# pcb-project.net
KiCad netlist of a schematic drawn in EasyEDA Pro
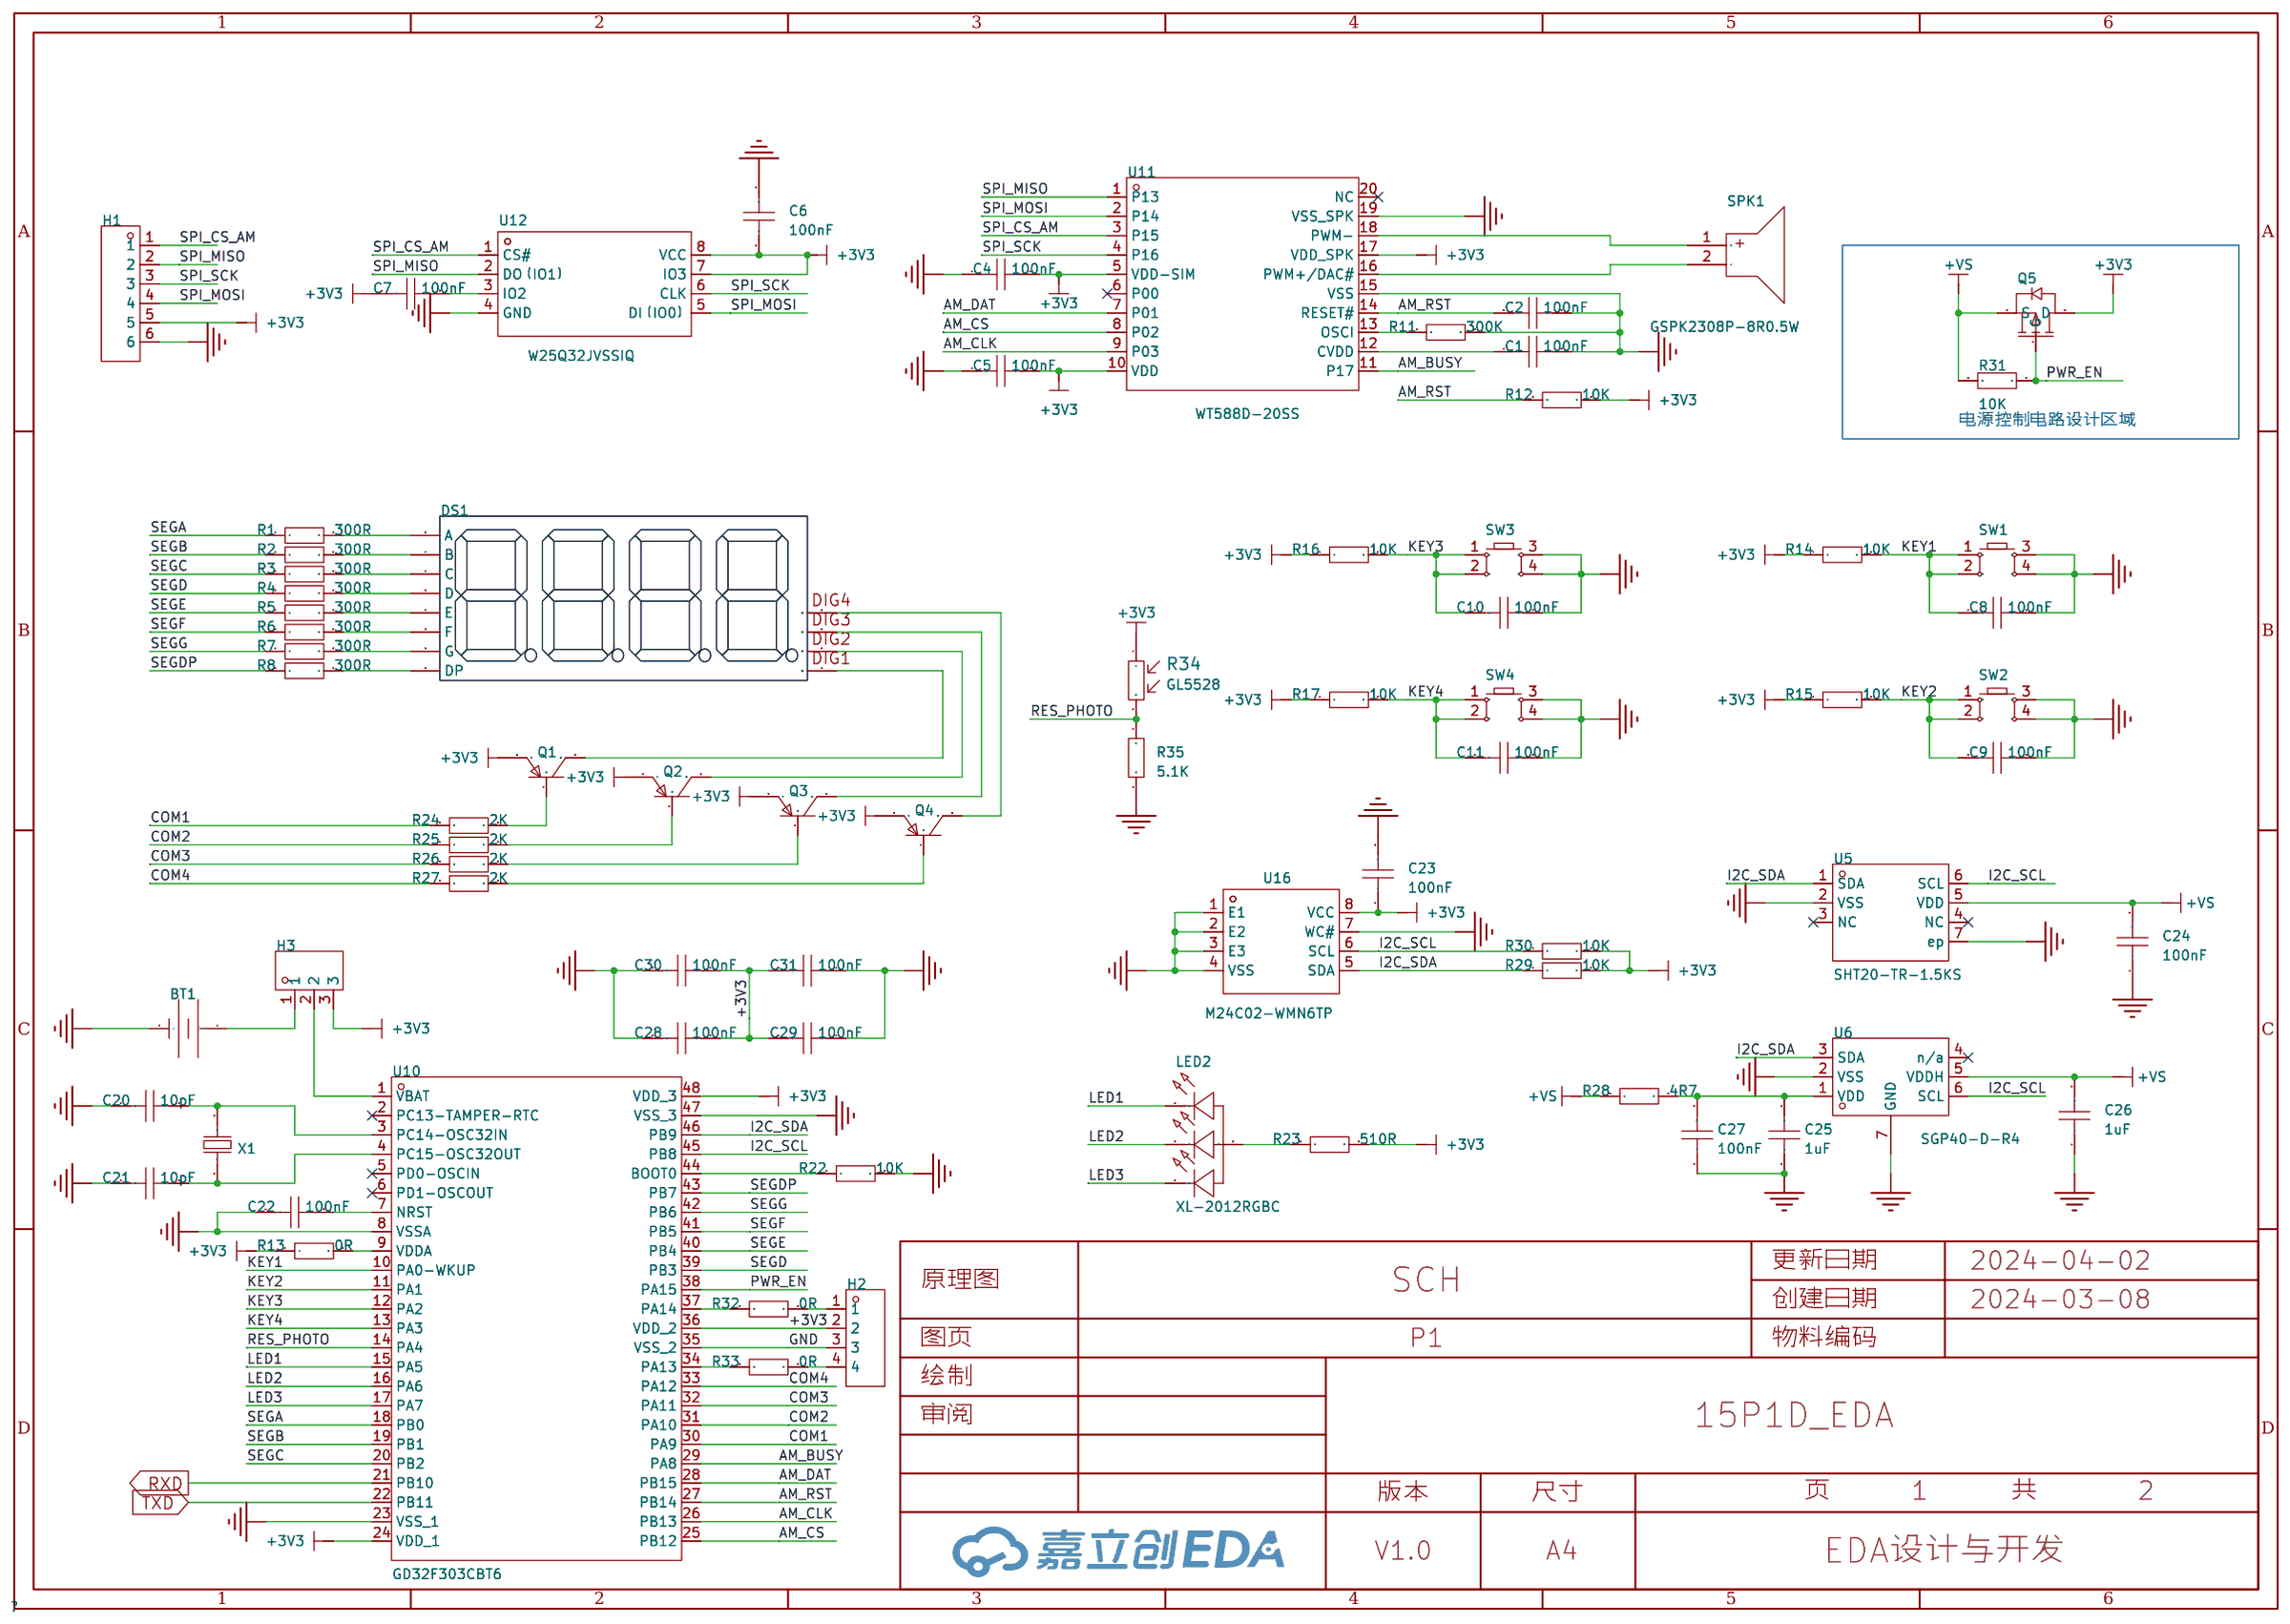
[diagram p0: P1]
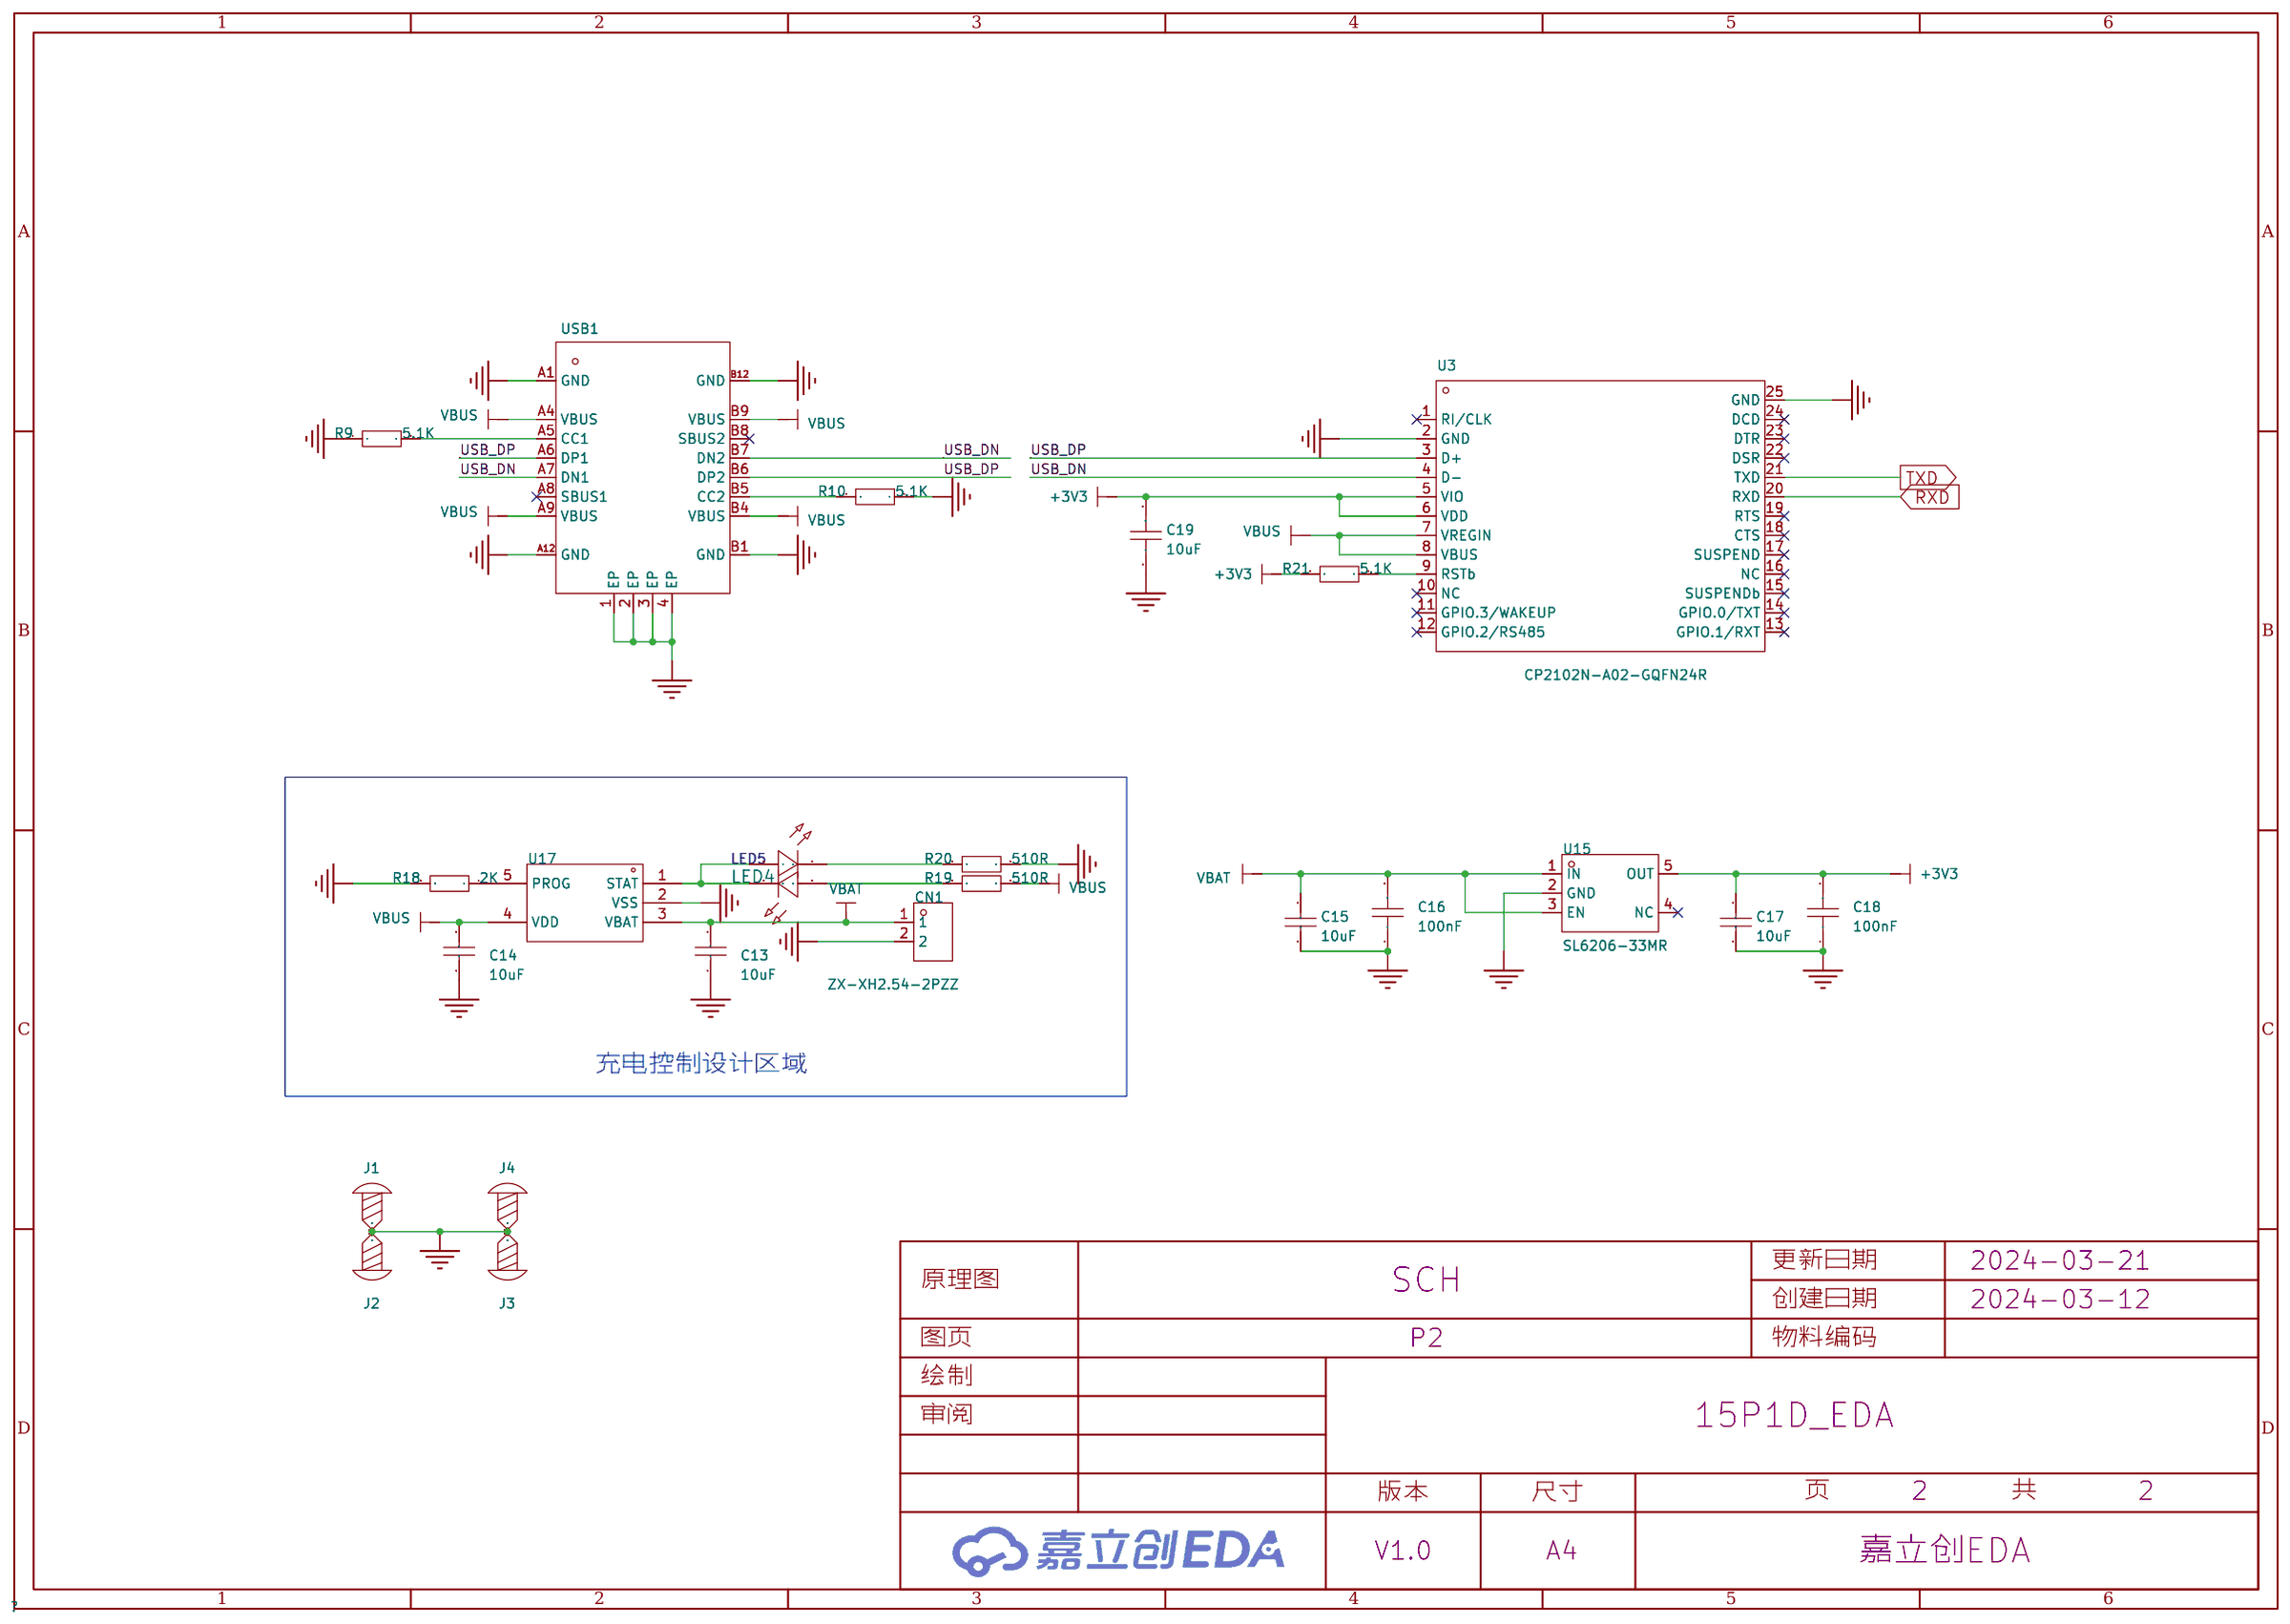
[diagram p1: P2]

(export (version "E")
  (design (tool "Eeschema 10.0.6"))
  (components
    (comp (ref "BT1")
      (value "BS-12-B3AA003")
      (footprint "easyedapro:BAT-SMD_BS-12-B3AA011")
      (description "连接器类型:电池底座;适用电池规格:CR1220;工作温度范围:-25°C~+85°C;")
      (fields (field (name "Manufacturer") "MYOUNG(美阳)"))
      (libsource (lib "easyedapro") (part "BS-12-B3AA003"))
    )
    (comp (ref "C1")
      (value "100nF")
      (footprint "easyedapro:C0805")
      (libsource (lib "easyedapro") (part "CapAcitance"))
    )
    (comp (ref "C2")
      (value "100nF")
      (footprint "easyedapro:C0805")
      (libsource (lib "easyedapro") (part "CapAcitance"))
    )
    (comp (ref "C4")
      (value "100nF")
      (footprint "easyedapro:C0805")
      (libsource (lib "easyedapro") (part "CapAcitance"))
    )
    (comp (ref "C5")
      (value "100nF")
      (footprint "easyedapro:C0805")
      (libsource (lib "easyedapro") (part "CapAcitance"))
    )
    (comp (ref "C6")
      (value "100nF")
      (footprint "easyedapro:C0805")
      (libsource (lib "easyedapro") (part "CapAcitance"))
    )
    (comp (ref "C7")
      (value "100nF")
      (footprint "easyedapro:C0805")
      (libsource (lib "easyedapro") (part "CapAcitance"))
    )
    (comp (ref "C8")
      (value "100nF")
      (footprint "easyedapro:C0805")
      (libsource (lib "easyedapro") (part "CapAcitance"))
    )
    (comp (ref "C9")
      (value "100nF")
      (footprint "easyedapro:C0805")
      (libsource (lib "easyedapro") (part "CapAcitance"))
    )
    (comp (ref "C10")
      (value "100nF")
      (footprint "easyedapro:C0805")
      (libsource (lib "easyedapro") (part "CapAcitance"))
    )
    (comp (ref "C11")
      (value "100nF")
      (footprint "easyedapro:C0805")
      (libsource (lib "easyedapro") (part "CapAcitance"))
    )
    (comp (ref "C20")
      (value "10pF")
      (footprint "easyedapro:C0805")
      (libsource (lib "easyedapro") (part "CapAcitance"))
    )
    (comp (ref "C21")
      (value "10pF")
      (footprint "easyedapro:C0805")
      (libsource (lib "easyedapro") (part "CapAcitance"))
    )
    (comp (ref "C22")
      (value "100nF")
      (footprint "easyedapro:C0805")
      (libsource (lib "easyedapro") (part "CapAcitance"))
    )
    (comp (ref "C23")
      (value "100nF")
      (footprint "easyedapro:C0805")
      (libsource (lib "easyedapro") (part "CapAcitance"))
    )
    (comp (ref "C24")
      (value "100nF")
      (footprint "easyedapro:C0805")
      (libsource (lib "easyedapro") (part "CapAcitance"))
    )
    (comp (ref "C25")
      (value "1uF")
      (footprint "easyedapro:C0805")
      (libsource (lib "easyedapro") (part "CapAcitance"))
    )
    (comp (ref "C26")
      (value "1uF")
      (footprint "easyedapro:C0805")
      (libsource (lib "easyedapro") (part "CapAcitance"))
    )
    (comp (ref "C27")
      (value "100nF")
      (footprint "easyedapro:C0805")
      (libsource (lib "easyedapro") (part "CapAcitance"))
    )
    (comp (ref "C28")
      (value "100nF")
      (footprint "easyedapro:C0805")
      (libsource (lib "easyedapro") (part "CapAcitance"))
    )
    (comp (ref "C29")
      (value "100nF")
      (footprint "easyedapro:C0805")
      (libsource (lib "easyedapro") (part "CapAcitance"))
    )
    (comp (ref "C30")
      (value "100nF")
      (footprint "easyedapro:C0805")
      (libsource (lib "easyedapro") (part "CapAcitance"))
    )
    (comp (ref "C31")
      (value "100nF")
      (footprint "easyedapro:C0805")
      (libsource (lib "easyedapro") (part "CapAcitance"))
    )
    (comp (ref "DS1")
      (value "~")
      (footprint "easyedapro:LED-SEG-TH_FJ5461AH")
      (libsource (lib "easyedapro") (part "LED_SEG_TH_0.56x4"))
    )
    (comp (ref "H1")
      (value "~")
      (footprint "easyedapro:HDR-TH_6P-P2.54-V-F")
      (libsource (lib "easyedapro") (part "Header-Female-2.54_1x6"))
    )
    (comp (ref "H2")
      (value "~")
      (footprint "easyedapro:HDR-TH_4P-P2.54-V-F")
      (libsource (lib "easyedapro") (part "2.54-1*4P母"))
    )
    (comp (ref "H3")
      (value "Jumper3")
      (footprint "easyedapro:HDR-TH_3P-P2.54-V-M-A")
      (libsource (lib "easyedapro") (part "JUMPER3"))
    )
    (comp (ref "LED2")
      (value "XL-2012RGBC")
      (footprint "easyedapro:LED-SMD_4P-L2.0-W1.3-BR")
      (fields (field (name "Manufacturer") "XINGLIGHT(成兴光)"))
      (libsource (lib "easyedapro") (part "XL-2012RGBC"))
    )
    (comp (ref "Q1")
      (value "~")
      (footprint "easyedapro:S8550P_SOT")
      (libsource (lib "easyedapro") (part "PNP"))
    )
    (comp (ref "Q2")
      (value "~")
      (footprint "easyedapro:S8550P_SOT")
      (libsource (lib "easyedapro") (part "PNP"))
    )
    (comp (ref "Q3")
      (value "~")
      (footprint "easyedapro:S8550P_SOT")
      (libsource (lib "easyedapro") (part "PNP"))
    )
    (comp (ref "Q4")
      (value "~")
      (footprint "easyedapro:S8550P_SOT")
      (libsource (lib "easyedapro") (part "PNP"))
    )
    (comp (ref "Q5")
      (value "~")
      (footprint "easyedapro:AO3401A_SOT-23-3")
      (libsource (lib "easyedapro") (part "P_MOS"))
    )
    (comp (ref "R1") (value "300R") (footprint "easyedapro:R0805") (libsource (lib "easyedapro") (part "电阻")))
    (comp (ref "R2") (value "300R") (footprint "easyedapro:R0805") (libsource (lib "easyedapro") (part "电阻")))
    (comp (ref "R3") (value "300R") (footprint "easyedapro:R0805") (libsource (lib "easyedapro") (part "电阻")))
    (comp (ref "R4") (value "300R") (footprint "easyedapro:R0805") (libsource (lib "easyedapro") (part "电阻")))
    (comp (ref "R5") (value "300R") (footprint "easyedapro:R0805") (libsource (lib "easyedapro") (part "电阻")))
    (comp (ref "R6") (value "300R") (footprint "easyedapro:R0805") (libsource (lib "easyedapro") (part "电阻")))
    (comp (ref "R7") (value "300R") (footprint "easyedapro:R0805") (libsource (lib "easyedapro") (part "电阻")))
    (comp (ref "R8") (value "300R") (footprint "easyedapro:R0805") (libsource (lib "easyedapro") (part "电阻")))
    (comp (ref "R11")
      (value "300K")
      (footprint "easyedapro:R0805")
      (libsource (lib "easyedapro") (part "电阻"))
    )
    (comp (ref "R12") (value "10K") (footprint "easyedapro:R0805") (libsource (lib "easyedapro") (part "电阻")))
    (comp (ref "R13") (value "0R") (footprint "easyedapro:R0805") (libsource (lib "easyedapro") (part "电阻")))
    (comp (ref "R14") (value "10K") (footprint "easyedapro:R0805") (libsource (lib "easyedapro") (part "电阻")))
    (comp (ref "R15") (value "10K") (footprint "easyedapro:R0805") (libsource (lib "easyedapro") (part "电阻")))
    (comp (ref "R16") (value "10K") (footprint "easyedapro:R0805") (libsource (lib "easyedapro") (part "电阻")))
    (comp (ref "R17") (value "10K") (footprint "easyedapro:R0805") (libsource (lib "easyedapro") (part "电阻")))
    (comp (ref "R22") (value "10K") (footprint "easyedapro:R0805") (libsource (lib "easyedapro") (part "电阻")))
    (comp (ref "R23")
      (value "510R")
      (footprint "easyedapro:R0805")
      (libsource (lib "easyedapro") (part "电阻"))
    )
    (comp (ref "R24") (value "2K") (footprint "easyedapro:R0805") (libsource (lib "easyedapro") (part "电阻")))
    (comp (ref "R25") (value "2K") (footprint "easyedapro:R0805") (libsource (lib "easyedapro") (part "电阻")))
    (comp (ref "R26") (value "2K") (footprint "easyedapro:R0805") (libsource (lib "easyedapro") (part "电阻")))
    (comp (ref "R27") (value "2K") (footprint "easyedapro:R0805") (libsource (lib "easyedapro") (part "电阻")))
    (comp (ref "R28") (value "4R7") (footprint "easyedapro:R0805") (libsource (lib "easyedapro") (part "电阻")))
    (comp (ref "R29") (value "10K") (footprint "easyedapro:R0805") (libsource (lib "easyedapro") (part "电阻")))
    (comp (ref "R30") (value "10K") (footprint "easyedapro:R0805") (libsource (lib "easyedapro") (part "电阻")))
    (comp (ref "R31") (value "10K") (footprint "easyedapro:R0805") (libsource (lib "easyedapro") (part "电阻")))
    (comp (ref "R32") (value "0R") (footprint "easyedapro:R0805") (libsource (lib "easyedapro") (part "电阻")))
    (comp (ref "R33") (value "0R") (footprint "easyedapro:R0805") (libsource (lib "easyedapro") (part "电阻")))
    (comp (ref "R34")
      (value "GL5528")
      (footprint "easyedapro:RES-TH_L5.1-W4.3-P3.40-D0.5")
      (description "暗电阻:1MΩ;亮电阻 @ 10Lux:8kΩ~20kΩ;光谱峰值(波长):540nm;")
      (fields (field (name "Manufacturer") "森霸"))
      (libsource (lib "easyedapro") (part "GL5528"))
    )
    (comp (ref "R35")
      (value "5.1K")
      (footprint "easyedapro:R0805")
      (libsource (lib "easyedapro") (part "电阻"))
    )
    (comp (ref "SPK1")
      (value "GSPK2308P-8R0.5W")
      (footprint "easyedapro:SPK-TH_BD23.0-P10.00-D0.8-L-RD")
      (fields (field (name "Manufacturer") "INGHAi(赢海)"))
      (libsource (lib "easyedapro") (part "GSPK2308P-8R0.5W"))
    )
    (comp (ref "SW1")
      (value "~")
      (footprint "easyedapro:Key_SMD_12x12x7.3")
      (libsource (lib "easyedapro") (part "轻触按键"))
    )
    (comp (ref "SW2")
      (value "~")
      (footprint "easyedapro:Key_SMD_12x12x7.3")
      (libsource (lib "easyedapro") (part "轻触按键"))
    )
    (comp (ref "SW3")
      (value "~")
      (footprint "easyedapro:Key_SMD_12x12x7.3")
      (libsource (lib "easyedapro") (part "轻触按键"))
    )
    (comp (ref "SW4")
      (value "~")
      (footprint "easyedapro:Key_SMD_12x12x7.3")
      (libsource (lib "easyedapro") (part "轻触按键"))
    )
    (comp (ref "U5")
      (value "SHT20-TR-1.5KS")
      (footprint "easyedapro:DFN-6_L3.0-W3.0-P0.95-TR-EP")
      (description "接口类型:I2C;")
      (fields (field (name "Manufacturer") "Sensirion(瑞士盛思锐)"))
      (libsource (lib "easyedapro") (part "SHT20"))
    )
    (comp (ref "U6")
      (value "SGP40-D-R4")
      (footprint "easyedapro:DFN-6_L2.4-W2.4-P0.80-TL-EP")
      (description "气体类型:空气质量;精度:-;")
      (fields (field (name "Manufacturer") "Sensirion(瑞士盛思锐)"))
      (libsource (lib "easyedapro") (part "SGP40-D-R4"))
    )
    (comp (ref "U10")
      (value "GD32F303CBT6")
      (footprint "easyedapro:LQFP-48_L7.0-W7.0-P0.50-LS9.0-BL")
      (description "CPU内核:CM4;程序存储容量:128KB;RAM总容量:32KB;GPIO端口数量:37;工作电压范围:-;CPU最大主频:120MHz;程序存储器类型:FLASH;")
      (fields (field (name "Manufacturer") "GigaDevice(兆易创新)"))
      (libsource (lib "easyedapro") (part "GD32F303CBT6"))
    )
    (comp (ref "U11")
      (value "WT588D-20SS")
      (footprint "easyedapro:SSOP-20_L7.2-W5.3-P0.65-LS7.8-BL")
      (description "高品质语音芯片")
      (fields (field (name "Manufacturer") "WT(唯创知音)"))
      (libsource (lib "easyedapro") (part "WT588D"))
    )
    (comp (ref "U12")
      (value "W25Q32JVSSIQ")
      (footprint "easyedapro:SOIC-8_L5.3-W5.3-P1.27-LS8.0-BL")
      (description "接口类型:SPI;存储容量:32Mbit;")
      (fields (field (name "Manufacturer") "WINBOND(华邦)"))
      (libsource (lib "easyedapro") (part "W25Q32JVSSIQ"))
    )
    (comp (ref "U16")
      (value "M24C02-WMN6TP")
      (footprint "easyedapro:SOIC-8_L4.9-W3.9-P1.27-LS6.0-BL")
      (description "接口类型:I2C;存储容量:2Kbit;")
      (fields (field (name "Manufacturer") "ST(意法半导体)"))
      (libsource (lib "easyedapro") (part "M24C02-WMN6TP"))
    )
    (comp (ref "X1")
      (value "32.768kHz")
      (footprint "easyedapro:FC-135R_L3.2-W1.5")
      (description "晶振类型:贴片晶振;频率:32.768kHz;常温频差:±20ppm;外接负载电容:12.5pF;")
      (fields (field (name "Manufacturer Part") "Q13FC13500004") (field (name "Manufacturer") "EPSON(爱普生)"))
      (libsource (lib "easyedapro") (part "Q13FC1350000400"))
    )
    (comp (ref "C13")
      (value "10uF")
      (footprint "easyedapro:C1206")
      (description "容值:10uF;精度:±10%;额定电压:50V;材质(温度系数):X5R;")
      (fields
        (field (name "Manufacturer Part") "CL31A106KBHNNNE")
        (field (name "Manufacturer") "SAMSUNG(三星)")
      )
      (libsource (lib "easyedapro") (part "CL31A106KBHNNNE"))
    )
    (comp (ref "C14")
      (value "10uF")
      (footprint "easyedapro:C1206")
      (description "容值:10uF;精度:±10%;额定电压:50V;材质(温度系数):X5R;")
      (fields
        (field (name "Manufacturer Part") "CL31A106KBHNNNE")
        (field (name "Manufacturer") "SAMSUNG(三星)")
      )
      (libsource (lib "easyedapro") (part "CL31A106KBHNNNE"))
    )
    (comp (ref "C15")
      (value "10uF")
      (footprint "easyedapro:C1206")
      (description "容值:10uF;精度:±10%;额定电压:50V;材质(温度系数):X5R;")
      (fields
        (field (name "Manufacturer Part") "CL31A106KBHNNNE")
        (field (name "Manufacturer") "SAMSUNG(三星)")
      )
      (libsource (lib "easyedapro") (part "CL31A106KBHNNNE"))
    )
    (comp (ref "C16")
      (value "100nF")
      (footprint "easyedapro:C0805")
      (libsource (lib "easyedapro") (part "CapAcitance"))
    )
    (comp (ref "C17")
      (value "10uF")
      (footprint "easyedapro:C1206")
      (description "容值:10uF;精度:±10%;额定电压:50V;材质(温度系数):X5R;")
      (fields
        (field (name "Manufacturer Part") "CL31A106KBHNNNE")
        (field (name "Manufacturer") "SAMSUNG(三星)")
      )
      (libsource (lib "easyedapro") (part "CL31A106KBHNNNE"))
    )
    (comp (ref "C18")
      (value "100nF")
      (footprint "easyedapro:C0805")
      (libsource (lib "easyedapro") (part "CapAcitance"))
    )
    (comp (ref "C19")
      (value "10uF")
      (footprint "easyedapro:C0805")
      (libsource (lib "easyedapro") (part "CapAcitance"))
    )
    (comp (ref "CN1")
      (value "ZX-XH2.54-2PZZ")
      (footprint "easyedapro:CONN-TH_2P-P2.50_HX25003-2A")
      (fields (field (name "Manufacturer") "Megastar(兆星)"))
      (libsource (lib "easyedapro") (part "ZX-XH2.54-2PZZ"))
    )
    (comp (ref "J1") (value "~") (footprint "easyedapro:M2螺丝") (libsource (lib "easyedapro") (part "螺丝孔")))
    (comp (ref "J2") (value "~") (footprint "easyedapro:M2螺丝") (libsource (lib "easyedapro") (part "螺丝孔")))
    (comp (ref "J3") (value "~") (footprint "easyedapro:M2螺丝") (libsource (lib "easyedapro") (part "螺丝孔")))
    (comp (ref "J4") (value "~") (footprint "easyedapro:M2螺丝") (libsource (lib "easyedapro") (part "螺丝孔")))
    (comp (ref "LED4")
      (value "~")
      (footprint "easyedapro:LED_0805")
      (libsource (lib "easyedapro") (part "LED_R"))
    )
    (comp (ref "LED5")
      (value "~")
      (footprint "easyedapro:LED_0805")
      (libsource (lib "easyedapro") (part "LED_G"))
    )
    (comp (ref "R9") (value "5.1K") (footprint "easyedapro:R0805") (libsource (lib "easyedapro") (part "电阻")))
    (comp (ref "R10")
      (value "5.1K")
      (footprint "easyedapro:R0805")
      (libsource (lib "easyedapro") (part "电阻"))
    )
    (comp (ref "R18") (value "2K") (footprint "easyedapro:R0805") (libsource (lib "easyedapro") (part "电阻")))
    (comp (ref "R19")
      (value "510R")
      (footprint "easyedapro:R0805")
      (libsource (lib "easyedapro") (part "电阻"))
    )
    (comp (ref "R20")
      (value "510R")
      (footprint "easyedapro:R0805")
      (libsource (lib "easyedapro") (part "电阻"))
    )
    (comp (ref "R21")
      (value "5.1K")
      (footprint "easyedapro:R0805")
      (libsource (lib "easyedapro") (part "电阻"))
    )
    (comp (ref "U3")
      (value "CP2102N-A02-GQFN24R")
      (footprint "easyedapro:QFN-24_L4.0-W4.0-P0.50-TL-EP2.6")
      (description "应用功能:USB转UART;接口协议:UART;")
      (fields (field (name "Manufacturer") "SKYWORKS/SILICON LABS(芯科)"))
      (libsource (lib "easyedapro") (part "CP2102N-A02-GQFN24R"))
    )
    (comp (ref "U15")
      (value "SL6206-33MR")
      (footprint "easyedapro:SOT-23-5_L2.9-W1.6-P0.95-LS2.8-BL")
      (description "输出类型:-;")
      (fields (field (name "Manufacturer") "Slkor(萨科微)"))
      (libsource (lib "easyedapro") (part "SL6206-33MR"))
    )
    (comp (ref "U17")
      (value "~")
      (footprint "easyedapro:SOP_BCON")
      (libsource (lib "easyedapro") (part "BCON"))
    )
    (comp (ref "USB1")
      (value "~")
      (footprint "easyedapro:USB_TYPE-C-16P")
      (libsource (lib "easyedapro") (part "USB_TYPE-C-16P"))
    )
  )
  (nets
    (net (code "1") (name "+3V3") (class "Default")
      (node (ref "C17") (pin "2") (pinfunction "2_2") (pintype "input"))
      (node (ref "C18") (pin "2") (pinfunction "2_2") (pintype "input"))
      (node (ref "C19") (pin "2") (pinfunction "2_2") (pintype "input"))
      (node (ref "C23") (pin "1") (pinfunction "1_1") (pintype "input"))
      (node (ref "C28") (pin "1") (pinfunction "1_1") (pintype "input"))
      (node (ref "C29") (pin "2") (pinfunction "2_2") (pintype "input"))
      (node (ref "C30") (pin "1") (pinfunction "1_1") (pintype "input"))
      (node (ref "C31") (pin "2") (pinfunction "2_2") (pintype "input"))
      (node (ref "C4") (pin "2") (pinfunction "2_2") (pintype "input"))
      (node (ref "C5") (pin "2") (pinfunction "2_2") (pintype "input"))
      (node (ref "C6") (pin "2") (pinfunction "2_2") (pintype "input"))
      (node (ref "C7") (pin "1") (pinfunction "1_1") (pintype "input"))
      (node (ref "H1") (pin "5") (pinfunction "5_5") (pintype "unspecified"))
      (node (ref "H2") (pin "2") (pinfunction "2_2") (pintype "unspecified"))
      (node (ref "H3") (pin "3") (pinfunction "3_3") (pintype "input"))
      (node (ref "Q1") (pin "2") (pinfunction "E_2") (pintype "input"))
      (node (ref "Q2") (pin "2") (pinfunction "E_2") (pintype "input"))
      (node (ref "Q3") (pin "2") (pinfunction "E_2") (pintype "input"))
      (node (ref "Q4") (pin "2") (pinfunction "E_2") (pintype "input"))
      (node (ref "Q5") (pin "3") (pinfunction "D_3") (pintype "input"))
      (node (ref "R12") (pin "2") (pinfunction "2_2") (pintype "input"))
      (node (ref "R13") (pin "1") (pinfunction "1_1") (pintype "input"))
      (node (ref "R14") (pin "1") (pinfunction "1_1") (pintype "input"))
      (node (ref "R15") (pin "1") (pinfunction "1_1") (pintype "input"))
      (node (ref "R16") (pin "1") (pinfunction "1_1") (pintype "input"))
      (node (ref "R17") (pin "1") (pinfunction "1_1") (pintype "input"))
      (node (ref "R21") (pin "2") (pinfunction "2_2") (pintype "input"))
      (node (ref "R23") (pin "2") (pinfunction "2_2") (pintype "input"))
      (node (ref "R29") (pin "2") (pinfunction "2_2") (pintype "input"))
      (node (ref "R30") (pin "2") (pinfunction "2_2") (pintype "input"))
      (node (ref "R34") (pin "1") (pinfunction "1_1") (pintype "input"))
      (node (ref "U10") (pin "24") (pinfunction "VDD_1_24") (pintype "unspecified"))
      (node (ref "U10") (pin "36") (pinfunction "VDD_2_36") (pintype "unspecified"))
      (node (ref "U10") (pin "48") (pinfunction "VDD_3_48") (pintype "unspecified"))
      (node (ref "U11") (pin "10") (pinfunction "VDD_10") (pintype "input"))
      (node (ref "U11") (pin "17") (pinfunction "VDD_SPK_17") (pintype "input"))
      (node (ref "U11") (pin "5") (pinfunction "VDD-SIM_5") (pintype "input"))
      (node (ref "U12") (pin "7") (pinfunction "IO3_7") (pintype "unspecified"))
      (node (ref "U12") (pin "8") (pinfunction "VCC_8") (pintype "unspecified"))
      (node (ref "U15") (pin "5") (pinfunction "OUT_5") (pintype "unspecified"))
      (node (ref "U16") (pin "8") (pinfunction "VCC_8") (pintype "unspecified"))
      (node (ref "U3") (pin "5") (pinfunction "VIO_5") (pintype "unspecified"))
      (node (ref "U3") (pin "6") (pinfunction "VDD_6") (pintype "unspecified"))
    )
    (net (code "2") (name "+VS") (class "Default")
      (node (ref "C24") (pin "2") (pinfunction "2_2") (pintype "input"))
      (node (ref "C26") (pin "2") (pinfunction "2_2") (pintype "input"))
      (node (ref "Q5") (pin "2") (pinfunction "S_2") (pintype "input"))
      (node (ref "R28") (pin "1") (pinfunction "1_1") (pintype "input"))
      (node (ref "R31") (pin "2") (pinfunction "2_2") (pintype "input"))
      (node (ref "U5") (pin "5") (pinfunction "VDD_5") (pintype "unspecified"))
      (node (ref "U6") (pin "5") (pinfunction "VDDH_5") (pintype "unspecified"))
    )
    (net (code "3") (name "AM_BUSY") (class "Default")
      (node (ref "U10") (pin "29") (pinfunction "PA8_29") (pintype "unspecified"))
      (node (ref "U11") (pin "11") (pinfunction "P17_11") (pintype "input"))
    )
    (net (code "4") (name "AM_CLK") (class "Default")
      (node (ref "U10") (pin "26") (pinfunction "PB13_26") (pintype "unspecified"))
      (node (ref "U11") (pin "9") (pinfunction "P03_9") (pintype "input"))
    )
    (net (code "5") (name "AM_CS") (class "Default")
      (node (ref "U10") (pin "25") (pinfunction "PB12_25") (pintype "unspecified"))
      (node (ref "U11") (pin "8") (pinfunction "P02_8") (pintype "input"))
    )
    (net (code "6") (name "AM_DAT") (class "Default")
      (node (ref "U10") (pin "28") (pinfunction "PB15_28") (pintype "unspecified"))
      (node (ref "U11") (pin "7") (pinfunction "P01_7") (pintype "input"))
    )
    (net (code "7") (name "AM_RST") (class "Default")
      (node (ref "C2") (pin "1") (pinfunction "1_1") (pintype "input"))
      (node (ref "R12") (pin "1") (pinfunction "1_1") (pintype "input"))
      (node (ref "U10") (pin "27") (pinfunction "PB14_27") (pintype "unspecified"))
      (node (ref "U11") (pin "14") (pinfunction "RESET#_14") (pintype "input"))
    )
    (net (code "8") (name "COM1") (class "Default")
      (node (ref "R24") (pin "1") (pinfunction "1_1") (pintype "input"))
      (node (ref "U10") (pin "30") (pinfunction "PA9_30") (pintype "unspecified"))
    )
    (net (code "9") (name "COM2") (class "Default")
      (node (ref "R25") (pin "1") (pinfunction "1_1") (pintype "input"))
      (node (ref "U10") (pin "31") (pinfunction "PA10_31") (pintype "unspecified"))
    )
    (net (code "10") (name "COM3") (class "Default")
      (node (ref "R26") (pin "1") (pinfunction "1_1") (pintype "input"))
      (node (ref "U10") (pin "32") (pinfunction "PA11_32") (pintype "unspecified"))
    )
    (net (code "11") (name "COM4") (class "Default")
      (node (ref "R27") (pin "1") (pinfunction "1_1") (pintype "input"))
      (node (ref "U10") (pin "33") (pinfunction "PA12_33") (pintype "unspecified"))
    )
    (net (code "12") (name "GND") (class "Default")
      (node (ref "BT1") (pin "2") (pinfunction "-_2") (pintype "unspecified"))
      (node (ref "C1") (pin "2") (pinfunction "2_2") (pintype "input"))
      (node (ref "C10") (pin "2") (pinfunction "2_2") (pintype "input"))
      (node (ref "C11") (pin "2") (pinfunction "2_2") (pintype "input"))
      (node (ref "C13") (pin "2") (pinfunction "2_2") (pintype "input"))
      (node (ref "C14") (pin "2") (pinfunction "2_2") (pintype "input"))
      (node (ref "C15") (pin "1") (pinfunction "1_1") (pintype "input"))
      (node (ref "C16") (pin "1") (pinfunction "1_1") (pintype "input"))
      (node (ref "C17") (pin "1") (pinfunction "1_1") (pintype "input"))
      (node (ref "C18") (pin "1") (pinfunction "1_1") (pintype "input"))
      (node (ref "C19") (pin "1") (pinfunction "1_1") (pintype "input"))
      (node (ref "C2") (pin "2") (pinfunction "2_2") (pintype "input"))
      (node (ref "C20") (pin "1") (pinfunction "1_1") (pintype "input"))
      (node (ref "C21") (pin "1") (pinfunction "1_1") (pintype "input"))
      (node (ref "C22") (pin "1") (pinfunction "1_1") (pintype "input"))
      (node (ref "C23") (pin "2") (pinfunction "2_2") (pintype "input"))
      (node (ref "C24") (pin "1") (pinfunction "1_1") (pintype "input"))
      (node (ref "C25") (pin "1") (pinfunction "1_1") (pintype "input"))
      (node (ref "C26") (pin "1") (pinfunction "1_1") (pintype "input"))
      (node (ref "C27") (pin "1") (pinfunction "1_1") (pintype "input"))
      (node (ref "C28") (pin "2") (pinfunction "2_2") (pintype "input"))
      (node (ref "C29") (pin "1") (pinfunction "1_1") (pintype "input"))
      (node (ref "C30") (pin "2") (pinfunction "2_2") (pintype "input"))
      (node (ref "C31") (pin "1") (pinfunction "1_1") (pintype "input"))
      (node (ref "C4") (pin "1") (pinfunction "1_1") (pintype "input"))
      (node (ref "C5") (pin "1") (pinfunction "1_1") (pintype "input"))
      (node (ref "C6") (pin "1") (pinfunction "1_1") (pintype "input"))
      (node (ref "C8") (pin "2") (pinfunction "2_2") (pintype "input"))
      (node (ref "C9") (pin "2") (pinfunction "2_2") (pintype "input"))
      (node (ref "CN1") (pin "2") (pinfunction "2_2") (pintype "unspecified"))
      (node (ref "H1") (pin "6") (pinfunction "6_6") (pintype "unspecified"))
      (node (ref "H2") (pin "3") (pinfunction "3_3") (pintype "unspecified"))
      (node (ref "J1") (pin "1") (pinfunction "1_1") (pintype "input"))
      (node (ref "J2") (pin "1") (pinfunction "1_1") (pintype "input"))
      (node (ref "J3") (pin "1") (pinfunction "1_1") (pintype "input"))
      (node (ref "J4") (pin "1") (pinfunction "1_1") (pintype "input"))
      (node (ref "R10") (pin "1") (pinfunction "1_1") (pintype "input"))
      (node (ref "R11") (pin "2") (pinfunction "2_2") (pintype "input"))
      (node (ref "R18") (pin "2") (pinfunction "2_2") (pintype "input"))
      (node (ref "R20") (pin "1") (pinfunction "1_1") (pintype "input"))
      (node (ref "R22") (pin "2") (pinfunction "2_2") (pintype "input"))
      (node (ref "R35") (pin "2") (pinfunction "2_2") (pintype "input"))
      (node (ref "R9") (pin "1") (pinfunction "1_1") (pintype "input"))
      (node (ref "SW1") (pin "3") (pinfunction "3_3") (pintype "input"))
      (node (ref "SW1") (pin "4") (pinfunction "4_4") (pintype "input"))
      (node (ref "SW2") (pin "3") (pinfunction "3_3") (pintype "input"))
      (node (ref "SW2") (pin "4") (pinfunction "4_4") (pintype "input"))
      (node (ref "SW3") (pin "3") (pinfunction "3_3") (pintype "input"))
      (node (ref "SW3") (pin "4") (pinfunction "4_4") (pintype "input"))
      (node (ref "SW4") (pin "3") (pinfunction "3_3") (pintype "input"))
      (node (ref "SW4") (pin "4") (pinfunction "4_4") (pintype "input"))
      (node (ref "U10") (pin "23") (pinfunction "VSS_1_23") (pintype "unspecified"))
      (node (ref "U10") (pin "35") (pinfunction "VSS_2_35") (pintype "unspecified"))
      (node (ref "U10") (pin "47") (pinfunction "VSS_3_47") (pintype "unspecified"))
      (node (ref "U10") (pin "8") (pinfunction "VSSA_8") (pintype "unspecified"))
      (node (ref "U11") (pin "15") (pinfunction "VSS_15") (pintype "input"))
      (node (ref "U11") (pin "19") (pinfunction "VSS_SPK_19") (pintype "input"))
      (node (ref "U12") (pin "4") (pinfunction "GND_4") (pintype "unspecified"))
      (node (ref "U15") (pin "2") (pinfunction "GND_2") (pintype "unspecified"))
      (node (ref "U16") (pin "1") (pinfunction "E1_1") (pintype "unspecified"))
      (node (ref "U16") (pin "2") (pinfunction "E2_2") (pintype "unspecified"))
      (node (ref "U16") (pin "3") (pinfunction "E3_3") (pintype "unspecified"))
      (node (ref "U16") (pin "4") (pinfunction "VSS_4") (pintype "unspecified"))
      (node (ref "U16") (pin "7") (pinfunction "WC#_7") (pintype "unspecified"))
      (node (ref "U17") (pin "2") (pinfunction "VSS_2") (pintype "input"))
      (node (ref "U3") (pin "2") (pinfunction "GND_2") (pintype "unspecified"))
      (node (ref "U3") (pin "25") (pinfunction "GND_25") (pintype "unspecified"))
      (node (ref "U5") (pin "2") (pinfunction "VSS_2") (pintype "unspecified"))
      (node (ref "U5") (pin "7") (pinfunction "ep_7") (pintype "unspecified"))
      (node (ref "U6") (pin "2") (pinfunction "VSS_2") (pintype "unspecified"))
      (node (ref "U6") (pin "7") (pinfunction "GND_7") (pintype "unspecified"))
      (node (ref "USB1") (pin "1") (pinfunction "EP_1") (pintype "input"))
      (node (ref "USB1") (pin "2") (pinfunction "EP_2") (pintype "input"))
      (node (ref "USB1") (pin "3") (pinfunction "EP_3") (pintype "input"))
      (node (ref "USB1") (pin "4") (pinfunction "EP_4") (pintype "input"))
      (node (ref "USB1") (pin "A1") (pinfunction "GND_A1") (pintype "input"))
      (node (ref "USB1") (pin "A12") (pinfunction "GND_A12") (pintype "input"))
      (node (ref "USB1") (pin "B1") (pinfunction "GND_B1") (pintype "input"))
      (node (ref "USB1") (pin "B12") (pinfunction "GND_B12") (pintype "input"))
    )
    (net (code "13") (name "I2C_SCL") (class "Default")
      (node (ref "R30") (pin "1") (pinfunction "1_1") (pintype "input"))
      (node (ref "U10") (pin "45") (pinfunction "PB8_45") (pintype "unspecified"))
      (node (ref "U16") (pin "6") (pinfunction "SCL_6") (pintype "unspecified"))
      (node (ref "U5") (pin "6") (pinfunction "SCL_6") (pintype "unspecified"))
      (node (ref "U6") (pin "6") (pinfunction "SCL_6") (pintype "unspecified"))
    )
    (net (code "14") (name "I2C_SDA") (class "Default")
      (node (ref "R29") (pin "1") (pinfunction "1_1") (pintype "input"))
      (node (ref "U10") (pin "46") (pinfunction "PB9_46") (pintype "unspecified"))
      (node (ref "U16") (pin "5") (pinfunction "SDA_5") (pintype "unspecified"))
      (node (ref "U5") (pin "1") (pinfunction "SDA_1") (pintype "unspecified"))
      (node (ref "U6") (pin "3") (pinfunction "SDA_3") (pintype "unspecified"))
    )
    (net (code "15") (name "KEY1") (class "Default")
      (node (ref "C8") (pin "1") (pinfunction "1_1") (pintype "input"))
      (node (ref "R14") (pin "2") (pinfunction "2_2") (pintype "input"))
      (node (ref "SW1") (pin "1") (pinfunction "1_1") (pintype "input"))
      (node (ref "SW1") (pin "2") (pinfunction "2_2") (pintype "input"))
      (node (ref "U10") (pin "10") (pinfunction "PA0-WKUP_10") (pintype "unspecified"))
    )
    (net (code "16") (name "KEY2") (class "Default")
      (node (ref "C9") (pin "1") (pinfunction "1_1") (pintype "input"))
      (node (ref "R15") (pin "2") (pinfunction "2_2") (pintype "input"))
      (node (ref "SW2") (pin "1") (pinfunction "1_1") (pintype "input"))
      (node (ref "SW2") (pin "2") (pinfunction "2_2") (pintype "input"))
      (node (ref "U10") (pin "11") (pinfunction "PA1_11") (pintype "unspecified"))
    )
    (net (code "17") (name "KEY3") (class "Default")
      (node (ref "C10") (pin "1") (pinfunction "1_1") (pintype "input"))
      (node (ref "R16") (pin "2") (pinfunction "2_2") (pintype "input"))
      (node (ref "SW3") (pin "1") (pinfunction "1_1") (pintype "input"))
      (node (ref "SW3") (pin "2") (pinfunction "2_2") (pintype "input"))
      (node (ref "U10") (pin "12") (pinfunction "PA2_12") (pintype "unspecified"))
    )
    (net (code "18") (name "KEY4") (class "Default")
      (node (ref "C11") (pin "1") (pinfunction "1_1") (pintype "input"))
      (node (ref "R17") (pin "2") (pinfunction "2_2") (pintype "input"))
      (node (ref "SW4") (pin "1") (pinfunction "1_1") (pintype "input"))
      (node (ref "SW4") (pin "2") (pinfunction "2_2") (pintype "input"))
      (node (ref "U10") (pin "13") (pinfunction "PA3_13") (pintype "unspecified"))
    )
    (net (code "19") (name "LED1") (class "Default")
      (node (ref "LED2") (pin "1") (pinfunction "1_1") (pintype "unspecified"))
      (node (ref "U10") (pin "15") (pinfunction "PA5_15") (pintype "unspecified"))
    )
    (net (code "20") (name "LED2") (class "Default")
      (node (ref "LED2") (pin "2") (pinfunction "2_2") (pintype "unspecified"))
      (node (ref "U10") (pin "16") (pinfunction "PA6_16") (pintype "unspecified"))
    )
    (net (code "21") (name "LED3") (class "Default")
      (node (ref "LED2") (pin "4") (pinfunction "4_4") (pintype "unspecified"))
      (node (ref "U10") (pin "17") (pinfunction "PA7_17") (pintype "unspecified"))
    )
    (net (code "22") (name "Net-(BT1-+)") (class "Default")
      (node (ref "BT1") (pin "1") (pinfunction "+_1") (pintype "unspecified"))
      (node (ref "H3") (pin "1") (pinfunction "1_1") (pintype "input"))
    )
    (net (code "23") (name "Net-(DS1-A)") (class "Default")
      (node (ref "DS1") (pin "11") (pinfunction "A_11") (pintype "input"))
      (node (ref "R1") (pin "2") (pinfunction "2_2") (pintype "input"))
    )
    (net (code "24") (name "Net-(DS1-B)") (class "Default")
      (node (ref "DS1") (pin "7") (pinfunction "B_7") (pintype "input"))
      (node (ref "R2") (pin "2") (pinfunction "2_2") (pintype "input"))
    )
    (net (code "25") (name "Net-(DS1-C)") (class "Default")
      (node (ref "DS1") (pin "4") (pinfunction "C_4") (pintype "input"))
      (node (ref "R3") (pin "2") (pinfunction "2_2") (pintype "input"))
    )
    (net (code "26") (name "Net-(DS1-D)") (class "Default")
      (node (ref "DS1") (pin "2") (pinfunction "D_2") (pintype "input"))
      (node (ref "R4") (pin "2") (pinfunction "2_2") (pintype "input"))
    )
    (net (code "27") (name "Net-(DS1-DIG1)") (class "Default")
      (node (ref "DS1") (pin "12") (pinfunction "DIG1_12") (pintype "input"))
      (node (ref "Q1") (pin "3") (pinfunction "C_3") (pintype "input"))
    )
    (net (code "28") (name "Net-(DS1-DIG2)") (class "Default")
      (node (ref "DS1") (pin "9") (pinfunction "DIG2_9") (pintype "input"))
      (node (ref "Q2") (pin "3") (pinfunction "C_3") (pintype "input"))
    )
    (net (code "29") (name "Net-(DS1-DIG3)") (class "Default")
      (node (ref "DS1") (pin "8") (pinfunction "DIG3_8") (pintype "input"))
      (node (ref "Q3") (pin "3") (pinfunction "C_3") (pintype "input"))
    )
    (net (code "30") (name "Net-(DS1-DIG4)") (class "Default")
      (node (ref "DS1") (pin "6") (pinfunction "DIG4_6") (pintype "input"))
      (node (ref "Q4") (pin "3") (pinfunction "C_3") (pintype "input"))
    )
    (net (code "31") (name "Net-(DS1-DP)") (class "Default")
      (node (ref "DS1") (pin "3") (pinfunction "DP_3") (pintype "input"))
      (node (ref "R8") (pin "2") (pinfunction "2_2") (pintype "input"))
    )
    (net (code "32") (name "Net-(DS1-E)") (class "Default")
      (node (ref "DS1") (pin "1") (pinfunction "E_1") (pintype "input"))
      (node (ref "R5") (pin "2") (pinfunction "2_2") (pintype "input"))
    )
    (net (code "33") (name "Net-(DS1-F)") (class "Default")
      (node (ref "DS1") (pin "10") (pinfunction "F_10") (pintype "input"))
      (node (ref "R6") (pin "2") (pinfunction "2_2") (pintype "input"))
    )
    (net (code "34") (name "Net-(DS1-G)") (class "Default")
      (node (ref "DS1") (pin "5") (pinfunction "G_5") (pintype "input"))
      (node (ref "R7") (pin "2") (pinfunction "2_2") (pintype "input"))
    )
    (net (code "35") (name "Net-(H2-Pad1)") (class "Default")
      (node (ref "H2") (pin "1") (pinfunction "1_1") (pintype "unspecified"))
      (node (ref "R32") (pin "2") (pinfunction "2_2") (pintype "input"))
    )
    (net (code "36") (name "Net-(H2-Pad4)") (class "Default")
      (node (ref "H2") (pin "4") (pinfunction "4_4") (pintype "unspecified"))
      (node (ref "R33") (pin "2") (pinfunction "2_2") (pintype "input"))
    )
    (net (code "37") (name "Net-(LED2-Pad3)") (class "Default")
      (node (ref "LED2") (pin "3") (pinfunction "3_3") (pintype "unspecified"))
      (node (ref "R23") (pin "1") (pinfunction "1_1") (pintype "input"))
    )
    (net (code "38") (name "Net-(LED4-A)") (class "Default")
      (node (ref "LED4") (pin "2") (pinfunction "A_2") (pintype "input"))
      (node (ref "R19") (pin "2") (pinfunction "2_2") (pintype "input"))
    )
    (net (code "39") (name "Net-(LED4-C)") (class "Default")
      (node (ref "LED4") (pin "1") (pinfunction "C_1") (pintype "input"))
      (node (ref "LED5") (pin "2") (pinfunction "A_2") (pintype "input"))
      (node (ref "U17") (pin "1") (pinfunction "STAT_1") (pintype "input"))
    )
    (net (code "40") (name "Net-(LED5-C)") (class "Default")
      (node (ref "LED5") (pin "1") (pinfunction "C_1") (pintype "input"))
      (node (ref "R20") (pin "2") (pinfunction "2_2") (pintype "input"))
    )
    (net (code "41") (name "Net-(Q1-B)") (class "Default")
      (node (ref "Q1") (pin "1") (pinfunction "B_1") (pintype "input"))
      (node (ref "R24") (pin "2") (pinfunction "2_2") (pintype "input"))
    )
    (net (code "42") (name "Net-(Q2-B)") (class "Default")
      (node (ref "Q2") (pin "1") (pinfunction "B_1") (pintype "input"))
      (node (ref "R25") (pin "2") (pinfunction "2_2") (pintype "input"))
    )
    (net (code "43") (name "Net-(Q3-B)") (class "Default")
      (node (ref "Q3") (pin "1") (pinfunction "B_1") (pintype "input"))
      (node (ref "R26") (pin "2") (pinfunction "2_2") (pintype "input"))
    )
    (net (code "44") (name "Net-(Q4-B)") (class "Default")
      (node (ref "Q4") (pin "1") (pinfunction "B_1") (pintype "input"))
      (node (ref "R27") (pin "2") (pinfunction "2_2") (pintype "input"))
    )
    (net (code "45") (name "Net-(SPK1-+)") (class "Default")
      (node (ref "SPK1") (pin "1") (pinfunction "+_1") (pintype "input"))
      (node (ref "U11") (pin "18") (pinfunction "PWM-_18") (pintype "input"))
    )
    (net (code "46") (name "Net-(SPK1--)") (class "Default")
      (node (ref "SPK1") (pin "2") (pinfunction "-_2") (pintype "input"))
      (node (ref "U11") (pin "16") (pinfunction "PWM+/DAC#_16") (pintype "input"))
    )
    (net (code "47") (name "Net-(U3-RSTb)") (class "Default")
      (node (ref "R21") (pin "1") (pinfunction "1_1") (pintype "input"))
      (node (ref "U3") (pin "9") (pinfunction "RSTb_9") (pintype "unspecified"))
    )
    (net (code "48") (name "Net-(U6-VDD)") (class "Default")
      (node (ref "C25") (pin "2") (pinfunction "2_2") (pintype "input"))
      (node (ref "C27") (pin "2") (pinfunction "2_2") (pintype "input"))
      (node (ref "R28") (pin "2") (pinfunction "2_2") (pintype "input"))
      (node (ref "U6") (pin "1") (pinfunction "VDD_1") (pintype "unspecified"))
    )
    (net (code "49") (name "Net-(U10-BOOT0)") (class "Default")
      (node (ref "R22") (pin "1") (pinfunction "1_1") (pintype "input"))
      (node (ref "U10") (pin "44") (pinfunction "BOOT0_44") (pintype "unspecified"))
    )
    (net (code "50") (name "Net-(U10-NRST)") (class "Default")
      (node (ref "C22") (pin "2") (pinfunction "2_2") (pintype "input"))
      (node (ref "U10") (pin "7") (pinfunction "NRST_7") (pintype "unspecified"))
    )
    (net (code "51") (name "Net-(U10-PA13)") (class "Default")
      (node (ref "R33") (pin "1") (pinfunction "1_1") (pintype "input"))
      (node (ref "U10") (pin "34") (pinfunction "PA13_34") (pintype "unspecified"))
    )
    (net (code "52") (name "Net-(U10-PA14)") (class "Default")
      (node (ref "R32") (pin "1") (pinfunction "1_1") (pintype "input"))
      (node (ref "U10") (pin "37") (pinfunction "PA14_37") (pintype "unspecified"))
    )
    (net (code "53") (name "Net-(U10-PC14-OSC32IN)") (class "Default")
      (node (ref "C20") (pin "2") (pinfunction "2_2") (pintype "input"))
      (node (ref "U10") (pin "3") (pinfunction "PC14-OSC32IN_3") (pintype "unspecified"))
      (node (ref "X1") (pin "1") (pinfunction "1_1") (pintype "unspecified"))
    )
    (net (code "54") (name "Net-(U10-PC15-OSC32OUT)") (class "Default")
      (node (ref "C21") (pin "2") (pinfunction "2_2") (pintype "input"))
      (node (ref "U10") (pin "4") (pinfunction "PC15-OSC32OUT_4") (pintype "unspecified"))
      (node (ref "X1") (pin "2") (pinfunction "2_2") (pintype "unspecified"))
    )
    (net (code "55") (name "Net-(U10-VBAT)") (class "Default")
      (node (ref "H3") (pin "2") (pinfunction "2_2") (pintype "input"))
      (node (ref "U10") (pin "1") (pinfunction "VBAT_1") (pintype "unspecified"))
    )
    (net (code "56") (name "Net-(U10-VDDA)") (class "Default")
      (node (ref "R13") (pin "2") (pinfunction "2_2") (pintype "input"))
      (node (ref "U10") (pin "9") (pinfunction "VDDA_9") (pintype "unspecified"))
    )
    (net (code "57") (name "Net-(U11-CVDD)") (class "Default")
      (node (ref "C1") (pin "1") (pinfunction "1_1") (pintype "input"))
      (node (ref "U11") (pin "12") (pinfunction "CVDD_12") (pintype "input"))
    )
    (net (code "58") (name "Net-(U11-OSCI)") (class "Default")
      (node (ref "R11") (pin "1") (pinfunction "1_1") (pintype "input"))
      (node (ref "U11") (pin "13") (pinfunction "OSCI_13") (pintype "input"))
    )
    (net (code "59") (name "Net-(U12-IO2)") (class "Default")
      (node (ref "C7") (pin "2") (pinfunction "2_2") (pintype "input"))
      (node (ref "U12") (pin "3") (pinfunction "IO2_3") (pintype "unspecified"))
    )
    (net (code "60") (name "Net-(U17-PROG)") (class "Default")
      (node (ref "R18") (pin "1") (pinfunction "1_1") (pintype "input"))
      (node (ref "U17") (pin "5") (pinfunction "PROG_5") (pintype "input"))
    )
    (net (code "61") (name "Net-(USB1-CC1)") (class "Default")
      (node (ref "R9") (pin "2") (pinfunction "2_2") (pintype "input"))
      (node (ref "USB1") (pin "A5") (pinfunction "CC1_A5") (pintype "input"))
    )
    (net (code "62") (name "Net-(USB1-CC2)") (class "Default")
      (node (ref "R10") (pin "2") (pinfunction "2_2") (pintype "input"))
      (node (ref "USB1") (pin "B5") (pinfunction "CC2_B5") (pintype "input"))
    )
    (net (code "63") (name "PWR_EN") (class "Default")
      (node (ref "Q5") (pin "1") (pinfunction "G_1") (pintype "input"))
      (node (ref "R31") (pin "1") (pinfunction "1_1") (pintype "input"))
      (node (ref "U10") (pin "38") (pinfunction "PA15_38") (pintype "unspecified"))
    )
    (net (code "64") (name "RES_PHOTO") (class "Default")
      (node (ref "R34") (pin "2") (pinfunction "2_2") (pintype "input"))
      (node (ref "R35") (pin "1") (pinfunction "1_1") (pintype "input"))
      (node (ref "U10") (pin "14") (pinfunction "PA4_14") (pintype "unspecified"))
    )
    (net (code "65") (name "RXD") (class "Default")
      (node (ref "U10") (pin "21") (pinfunction "PB10_21") (pintype "unspecified"))
      (node (ref "U3") (pin "20") (pinfunction "RXD_20") (pintype "unspecified"))
    )
    (net (code "66") (name "SEGA") (class "Default")
      (node (ref "R1") (pin "1") (pinfunction "1_1") (pintype "input"))
      (node (ref "U10") (pin "18") (pinfunction "PB0_18") (pintype "unspecified"))
    )
    (net (code "67") (name "SEGB") (class "Default")
      (node (ref "R2") (pin "1") (pinfunction "1_1") (pintype "input"))
      (node (ref "U10") (pin "19") (pinfunction "PB1_19") (pintype "unspecified"))
    )
    (net (code "68") (name "SEGC") (class "Default")
      (node (ref "R3") (pin "1") (pinfunction "1_1") (pintype "input"))
      (node (ref "U10") (pin "20") (pinfunction "PB2_20") (pintype "unspecified"))
    )
    (net (code "69") (name "SEGD") (class "Default")
      (node (ref "R4") (pin "1") (pinfunction "1_1") (pintype "input"))
      (node (ref "U10") (pin "39") (pinfunction "PB3_39") (pintype "unspecified"))
    )
    (net (code "70") (name "SEGDP") (class "Default")
      (node (ref "R8") (pin "1") (pinfunction "1_1") (pintype "input"))
      (node (ref "U10") (pin "43") (pinfunction "PB7_43") (pintype "unspecified"))
    )
    (net (code "71") (name "SEGE") (class "Default")
      (node (ref "R5") (pin "1") (pinfunction "1_1") (pintype "input"))
      (node (ref "U10") (pin "40") (pinfunction "PB4_40") (pintype "unspecified"))
    )
    (net (code "72") (name "SEGF") (class "Default")
      (node (ref "R6") (pin "1") (pinfunction "1_1") (pintype "input"))
      (node (ref "U10") (pin "41") (pinfunction "PB5_41") (pintype "unspecified"))
    )
    (net (code "73") (name "SEGG") (class "Default")
      (node (ref "R7") (pin "1") (pinfunction "1_1") (pintype "input"))
      (node (ref "U10") (pin "42") (pinfunction "PB6_42") (pintype "unspecified"))
    )
    (net (code "74") (name "SPI_CS_AM") (class "Default")
      (node (ref "H1") (pin "1") (pinfunction "1_1") (pintype "unspecified"))
      (node (ref "U11") (pin "3") (pinfunction "P15_3") (pintype "input"))
      (node (ref "U12") (pin "1") (pinfunction "CS#_1") (pintype "unspecified"))
    )
    (net (code "75") (name "SPI_MISO") (class "Default")
      (node (ref "H1") (pin "2") (pinfunction "2_2") (pintype "unspecified"))
      (node (ref "U11") (pin "1") (pinfunction "P13_1") (pintype "input"))
      (node (ref "U12") (pin "2") (pinfunction "DO（IO1）_2") (pintype "unspecified"))
    )
    (net (code "76") (name "SPI_MOSI") (class "Default")
      (node (ref "H1") (pin "4") (pinfunction "4_4") (pintype "unspecified"))
      (node (ref "U11") (pin "2") (pinfunction "P14_2") (pintype "input"))
      (node (ref "U12") (pin "5") (pinfunction "DI（IO0）_5") (pintype "unspecified"))
    )
    (net (code "77") (name "SPI_SCK") (class "Default")
      (node (ref "H1") (pin "3") (pinfunction "3_3") (pintype "unspecified"))
      (node (ref "U11") (pin "4") (pinfunction "P16_4") (pintype "input"))
      (node (ref "U12") (pin "6") (pinfunction "CLK_6") (pintype "unspecified"))
    )
    (net (code "78") (name "TXD") (class "Default")
      (node (ref "U10") (pin "22") (pinfunction "PB11_22") (pintype "unspecified"))
      (node (ref "U3") (pin "21") (pinfunction "TXD_21") (pintype "unspecified"))
    )
    (net (code "79") (name "USB_DN") (class "Default")
      (node (ref "U3") (pin "4") (pinfunction "D-_4") (pintype "unspecified"))
      (node (ref "USB1") (pin "A7") (pinfunction "DN1_A7") (pintype "input"))
      (node (ref "USB1") (pin "B7") (pinfunction "DN2_B7") (pintype "input"))
    )
    (net (code "80") (name "USB_DP") (class "Default")
      (node (ref "U3") (pin "3") (pinfunction "D+_3") (pintype "unspecified"))
      (node (ref "USB1") (pin "A6") (pinfunction "DP1_A6") (pintype "input"))
      (node (ref "USB1") (pin "B6") (pinfunction "DP2_B6") (pintype "input"))
    )
    (net (code "81") (name "VBAT") (class "Default")
      (node (ref "C13") (pin "1") (pinfunction "1_1") (pintype "input"))
      (node (ref "C15") (pin "2") (pinfunction "2_2") (pintype "input"))
      (node (ref "C16") (pin "2") (pinfunction "2_2") (pintype "input"))
      (node (ref "CN1") (pin "1") (pinfunction "1_1") (pintype "unspecified"))
      (node (ref "U15") (pin "1") (pinfunction "IN_1") (pintype "unspecified"))
      (node (ref "U15") (pin "3") (pinfunction "EN_3") (pintype "unspecified"))
      (node (ref "U17") (pin "3") (pinfunction "VBAT_3") (pintype "input"))
    )
    (net (code "82") (name "VBUS") (class "Default")
      (node (ref "C14") (pin "1") (pinfunction "1_1") (pintype "input"))
      (node (ref "R19") (pin "1") (pinfunction "1_1") (pintype "input"))
      (node (ref "U17") (pin "4") (pinfunction "VDD_4") (pintype "input"))
      (node (ref "U3") (pin "7") (pinfunction "VREGIN_7") (pintype "unspecified"))
      (node (ref "U3") (pin "8") (pinfunction "VBUS_8") (pintype "unspecified"))
      (node (ref "USB1") (pin "A4") (pinfunction "VBUS_A4") (pintype "input"))
      (node (ref "USB1") (pin "A9") (pinfunction "VBUS_A9") (pintype "input"))
      (node (ref "USB1") (pin "B4") (pinfunction "VBUS_B4") (pintype "input"))
      (node (ref "USB1") (pin "B9") (pinfunction "VBUS_B9") (pintype "input"))
    )
    (net (code "83") (name "unconnected-(U3-CTS-Pad18)") (class "Default")
      (node (ref "U3") (pin "18") (pinfunction "CTS_18") (pintype "unspecified+no_connect"))
    )
    (net (code "84") (name "unconnected-(U3-DCD-Pad24)") (class "Default")
      (node (ref "U3") (pin "24") (pinfunction "DCD_24") (pintype "unspecified+no_connect"))
    )
    (net (code "85") (name "unconnected-(U3-DSR-Pad22)") (class "Default")
      (node (ref "U3") (pin "22") (pinfunction "DSR_22") (pintype "unspecified+no_connect"))
    )
    (net (code "86") (name "unconnected-(U3-DTR-Pad23)") (class "Default")
      (node (ref "U3") (pin "23") (pinfunction "DTR_23") (pintype "unspecified+no_connect"))
    )
    (net (code "87") (name "unconnected-(U3-GPIO.0{slash}TXT-Pad14)") (class "Default")
      (node (ref "U3") (pin "14") (pinfunction "GPIO.0/TXT_14") (pintype "unspecified+no_connect"))
    )
    (net (code "88") (name "unconnected-(U3-GPIO.1{slash}RXT-Pad13)") (class "Default")
      (node (ref "U3") (pin "13") (pinfunction "GPIO.1/RXT_13") (pintype "unspecified+no_connect"))
    )
    (net (code "89") (name "unconnected-(U3-GPIO.2{slash}RS485-Pad12)") (class "Default")
      (node (ref "U3") (pin "12") (pinfunction "GPIO.2/RS485_12") (pintype "unspecified+no_connect"))
    )
    (net (code "90") (name "unconnected-(U3-GPIO.3{slash}WAKEUP-Pad11)") (class "Default")
      (node (ref "U3") (pin "11") (pinfunction "GPIO.3/WAKEUP_11") (pintype "unspecified+no_connect"))
    )
    (net (code "91") (name "unconnected-(U3-NC-Pad10)") (class "Default")
      (node (ref "U3") (pin "10") (pinfunction "NC_10") (pintype "unspecified+no_connect"))
    )
    (net (code "92") (name "unconnected-(U3-NC-Pad16)") (class "Default")
      (node (ref "U3") (pin "16") (pinfunction "NC_16") (pintype "unspecified+no_connect"))
    )
    (net (code "93") (name "unconnected-(U3-RI{slash}CLK-Pad1)") (class "Default")
      (node (ref "U3") (pin "1") (pinfunction "RI/CLK_1") (pintype "unspecified+no_connect"))
    )
    (net (code "94") (name "unconnected-(U3-RTS-Pad19)") (class "Default")
      (node (ref "U3") (pin "19") (pinfunction "RTS_19") (pintype "unspecified+no_connect"))
    )
    (net (code "95") (name "unconnected-(U3-SUSPEND-Pad17)") (class "Default")
      (node (ref "U3") (pin "17") (pinfunction "SUSPEND_17") (pintype "unspecified+no_connect"))
    )
    (net (code "96") (name "unconnected-(U3-SUSPENDb-Pad15)") (class "Default")
      (node (ref "U3") (pin "15") (pinfunction "SUSPENDb_15") (pintype "unspecified+no_connect"))
    )
    (net (code "97") (name "unconnected-(U5-NC-Pad3)") (class "Default")
      (node (ref "U5") (pin "3") (pinfunction "NC_3") (pintype "unspecified+no_connect"))
    )
    (net (code "98") (name "unconnected-(U5-NC-Pad4)") (class "Default")
      (node (ref "U5") (pin "4") (pinfunction "NC_4") (pintype "unspecified+no_connect"))
    )
    (net (code "99") (name "unconnected-(U6-n{slash}a-Pad4)") (class "Default")
      (node (ref "U6") (pin "4") (pinfunction "n/a_4") (pintype "unspecified+no_connect"))
    )
    (net (code "100") (name "unconnected-(U10-PC13-TAMPER-RTC-Pad2)") (class "Default")
      (node (ref "U10") (pin "2") (pinfunction "PC13-TAMPER-RTC_2") (pintype "unspecified+no_connect"))
    )
    (net (code "101") (name "unconnected-(U10-PD0-OSCIN-Pad5)") (class "Default")
      (node (ref "U10") (pin "5") (pinfunction "PD0-OSCIN_5") (pintype "unspecified+no_connect"))
    )
    (net (code "102") (name "unconnected-(U10-PD1-OSCOUT-Pad6)") (class "Default")
      (node (ref "U10") (pin "6") (pinfunction "PD1-OSCOUT_6") (pintype "unspecified+no_connect"))
    )
    (net (code "103") (name "unconnected-(U11-NC-Pad20)") (class "Default")
      (node (ref "U11") (pin "20") (pinfunction "NC_20") (pintype "input+no_connect"))
    )
    (net (code "104") (name "unconnected-(U11-P00-Pad6)") (class "Default")
      (node (ref "U11") (pin "6") (pinfunction "P00_6") (pintype "input+no_connect"))
    )
    (net (code "105") (name "unconnected-(U15-NC-Pad4)") (class "Default")
      (node (ref "U15") (pin "4") (pinfunction "NC_4") (pintype "unspecified+no_connect"))
    )
    (net (code "106") (name "unconnected-(USB1-SBUS1-PadA8)") (class "Default")
      (node (ref "USB1") (pin "A8") (pinfunction "SBUS1_A8") (pintype "input+no_connect"))
    )
    (net (code "107") (name "unconnected-(USB1-SBUS2-PadB8)") (class "Default")
      (node (ref "USB1") (pin "B8") (pinfunction "SBUS2_B8") (pintype "input+no_connect"))
    )
  )
)
